# SipPuffDuoOutputsATtiny84MOSFET.net
KiCad netlist of a schematic drawn in EAGLE
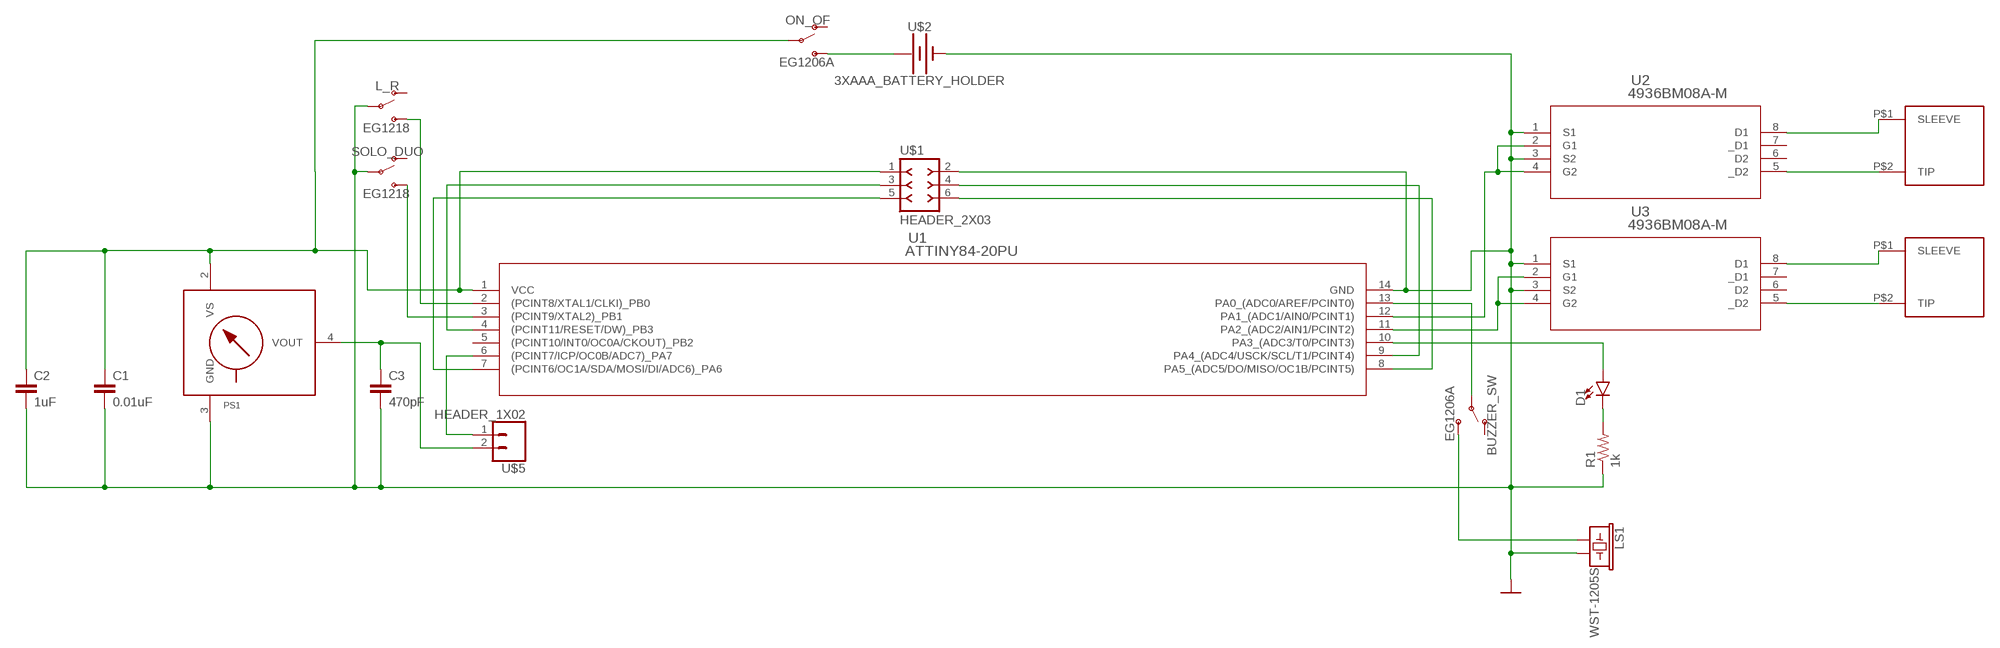
[diagram p0: schematic, sheet 1]

(export (version "E")
  (design (tool "Eeschema 10.0.6"))
  (components
    (comp (ref "BUZZER_SW")
      (value "EG1206A")
      (footprint "eagle-import:EG1206A")
      (libsource (lib "eagle-import") (part "EG1206A"))
    )
    (comp (ref "C1")
      (value "0.01uF")
      (footprint "eagle-import:CAP-PTH-SMALL-KIT")
      (libsource (lib "eagle-import") (part "0.1UF-KIT-EZ-50V-20%"))
    )
    (comp (ref "C2")
      (value "1uF")
      (footprint "eagle-import:CAP-PTH-SMALL-KIT")
      (libsource (lib "eagle-import") (part "0.1UF-KIT-EZ-50V-20%"))
    )
    (comp (ref "C3")
      (value "470pF")
      (footprint "eagle-import:CAP-PTH-SMALL-KIT")
      (libsource (lib "eagle-import") (part "0.1UF-KIT-EZ-50V-20%"))
    )
    (comp (ref "D1")
      (value "LED5MM")
      (footprint "eagle-import:LED_5MM")
      (libsource (lib "eagle-import") (part "LED5MM"))
    )
    (comp (ref "LS1")
      (value "WST-1205S")
      (footprint "eagle-import:BUZZER-12MM")
      (libsource (lib "eagle-import") (part "BUZZER-PTH"))
    )
    (comp (ref "L_R")
      (value "EG1218")
      (footprint "eagle-import:EG1218")
      (libsource (lib "eagle-import") (part "EG1218"))
    )
    (comp (ref "ON_OF")
      (value "EG1206A")
      (footprint "eagle-import:EG1206A")
      (libsource (lib "eagle-import") (part "EG1206A"))
    )
    (comp (ref "PS1")
      (value "MPX-1351")
      (footprint "eagle-import:1351")
      (libsource (lib "eagle-import") (part "MPX-1351"))
    )
    (comp (ref "R1")
      (value "1k")
      (footprint "eagle-import:RESISTOR_0207_10")
      (libsource (lib "eagle-import") (part "RESISTOR_R-US_"))
    )
    (comp (ref "SOLO_DUO")
      (value "EG1218")
      (footprint "eagle-import:EG1218")
      (libsource (lib "eagle-import") (part "EG1218"))
    )
    (comp (ref "U$1")
      (value "HEADER_2X03")
      (footprint "eagle-import:2X3")
      (libsource (lib "eagle-import") (part "HEADER_2X03"))
    )
    (comp (ref "U$2")
      (value "3XAAA_BATTERY_HOLDER")
      (footprint "eagle-import:3XAAA_BATTERY_HOLDER")
      (libsource (lib "eagle-import") (part "3XAAA_BATTERY_HOLDER"))
    )
    (comp (ref "U$3")
      (value "MONO_WIRE")
      (footprint "eagle-import:MONO_WIRE")
      (libsource (lib "eagle-import") (part "MONO_WIRE"))
    )
    (comp (ref "U$4")
      (value "MONO_WIRE")
      (footprint "eagle-import:MONO_WIRE")
      (libsource (lib "eagle-import") (part "MONO_WIRE"))
    )
    (comp (ref "U$5")
      (value "HEADER_1X02")
      (footprint "eagle-import:1X02")
      (libsource (lib "eagle-import") (part "HEADER_1X02"))
    )
    (comp (ref "U1")
      (value "ATTINY84-20PU")
      (footprint "eagle-import:14P3")
      (fields (field (name "MANUFACTURER_PART_NUMBER") "ATTINY8420PU"))
      (libsource (lib "eagle-import") (part "ATTINY84-20PU"))
    )
    (comp (ref "U2")
      (value "4936BM08A-M")
      (footprint "eagle-import:M08A-M")
      (fields (field (name "MANUFACTURER_PART_NUMBER") "LM34DM"))
      (libsource (lib "eagle-import") (part "4936BM08A-M"))
    )
    (comp (ref "U3")
      (value "4936BM08A-M")
      (footprint "eagle-import:M08A-M")
      (fields (field (name "MANUFACTURER_PART_NUMBER") "LM34DM"))
      (libsource (lib "eagle-import") (part "4936BM08A-M"))
    )
  )
  (nets
    (net (code "1") (name "GND") (class "Default")
      (node (ref "C1") (pin "2") (pinfunction "2_2") (pintype "passive"))
      (node (ref "C2") (pin "2") (pinfunction "2_2") (pintype "passive"))
      (node (ref "C3") (pin "2") (pinfunction "2_2") (pintype "passive"))
      (node (ref "LS1") (pin "-") (pinfunction "2_-") (pintype "passive"))
      (node (ref "L_R") (pin "2") (pinfunction "P_2") (pintype "passive"))
      (node (ref "PS1") (pin "3") (pinfunction "GND_3") (pintype "power_in"))
      (node (ref "R1") (pin "1") (pinfunction "1_1") (pintype "passive"))
      (node (ref "SOLO_DUO") (pin "2") (pinfunction "P_2") (pintype "passive"))
      (node (ref "U$1") (pin "2") (pinfunction "2_2") (pintype "passive"))
      (node (ref "U$2") (pin "P$2") (pinfunction "-_P$2") (pintype "power_in"))
      (node (ref "U1") (pin "14") (pinfunction "GND_14") (pintype "power_in"))
      (node (ref "U2") (pin "1") (pinfunction "S1_1") (pintype "output"))
      (node (ref "U2") (pin "3") (pinfunction "S2_3") (pintype "passive"))
      (node (ref "U3") (pin "1") (pinfunction "S1_1") (pintype "output"))
      (node (ref "U3") (pin "3") (pinfunction "S2_3") (pintype "passive"))
    )
    (net (code "2") (name "Net-(BUZZER_SW-P)") (class "Default")
      (node (ref "BUZZER_SW") (pin "2") (pinfunction "P_2") (pintype "passive"))
      (node (ref "U1") (pin "13") (pinfunction "PA0_(ADC0/AREF/PCINT0)_13") (pintype "bidirectional"))
    )
    (net (code "3") (name "Net-(BUZZER_SW-S)") (class "Default")
      (node (ref "BUZZER_SW") (pin "3") (pinfunction "S_3") (pintype "passive"))
      (node (ref "LS1") (pin "+") (pinfunction "1_+") (pintype "passive"))
    )
    (net (code "4") (name "Net-(D1-C)") (class "Default")
      (node (ref "D1") (pin "K") (pinfunction "C_K") (pintype "passive"))
      (node (ref "R1") (pin "2") (pinfunction "2_2") (pintype "passive"))
    )
    (net (code "5") (name "Net-(L_R-S)") (class "Default")
      (node (ref "L_R") (pin "3") (pinfunction "S_3") (pintype "passive"))
      (node (ref "U1") (pin "2") (pinfunction "(PCINT8/XTAL1/CLKI)_PB0_2") (pintype "bidirectional"))
    )
    (net (code "6") (name "Net-(ON_OF-P)") (class "Default")
      (node (ref "C1") (pin "1") (pinfunction "1_1") (pintype "passive"))
      (node (ref "C2") (pin "1") (pinfunction "1_1") (pintype "passive"))
      (node (ref "ON_OF") (pin "2") (pinfunction "P_2") (pintype "passive"))
      (node (ref "PS1") (pin "2") (pinfunction "VS_2") (pintype "power_in"))
      (node (ref "U$1") (pin "1") (pinfunction "1_1") (pintype "passive"))
      (node (ref "U1") (pin "1") (pinfunction "VCC_1") (pintype "power_in"))
    )
    (net (code "7") (name "Net-(ON_OF-S)") (class "Default")
      (node (ref "ON_OF") (pin "3") (pinfunction "S_3") (pintype "passive"))
      (node (ref "U$2") (pin "P$1") (pinfunction "+_P$1") (pintype "power_in"))
    )
    (net (code "8") (name "Net-(PS1-VOUT)") (class "Default")
      (node (ref "C3") (pin "1") (pinfunction "1_1") (pintype "passive"))
      (node (ref "PS1") (pin "4") (pinfunction "VOUT_4") (pintype "output"))
      (node (ref "U$5") (pin "2") (pinfunction "2_2") (pintype "passive"))
    )
    (net (code "9") (name "Net-(SOLO_DUO-S)") (class "Default")
      (node (ref "SOLO_DUO") (pin "3") (pinfunction "S_3") (pintype "passive"))
      (node (ref "U1") (pin "3") (pinfunction "(PCINT9/XTAL2)_PB1_3") (pintype "bidirectional"))
    )
    (net (code "10") (name "Net-(U$3-SLEEVE)") (class "Default")
      (node (ref "U$3") (pin "P$1") (pinfunction "SLEEVE_P$1") (pintype "bidirectional"))
      (node (ref "U2") (pin "8") (pinfunction "D1_8") (pintype "input"))
    )
    (net (code "11") (name "Net-(U$3-TIP)") (class "Default")
      (node (ref "U$3") (pin "P$2") (pinfunction "TIP_P$2") (pintype "bidirectional"))
      (node (ref "U2") (pin "5") (pinfunction "_D2_5") (pintype "passive"))
    )
    (net (code "12") (name "Net-(U$4-SLEEVE)") (class "Default")
      (node (ref "U$4") (pin "P$1") (pinfunction "SLEEVE_P$1") (pintype "bidirectional"))
      (node (ref "U3") (pin "8") (pinfunction "D1_8") (pintype "input"))
    )
    (net (code "13") (name "Net-(U$4-TIP)") (class "Default")
      (node (ref "U$4") (pin "P$2") (pinfunction "TIP_P$2") (pintype "bidirectional"))
      (node (ref "U3") (pin "5") (pinfunction "_D2_5") (pintype "passive"))
    )
    (net (code "14") (name "Net-(U1-(PCINT6{slash}OC1A{slash}SDA{slash}MOSI{slash}DI{slash}ADC6)_PA6)") (class "Default")
      (node (ref "U$1") (pin "5") (pinfunction "5_5") (pintype "passive"))
      (node (ref "U1") (pin "7") (pinfunction "(PCINT6/OC1A/SDA/MOSI/DI/ADC6)_PA6_7") (pintype "bidirectional"))
    )
    (net (code "15") (name "Net-(U1-(PCINT7{slash}ICP{slash}OC0B{slash}ADC7)_PA7)") (class "Default")
      (node (ref "U$5") (pin "1") (pinfunction "1_1") (pintype "passive"))
      (node (ref "U1") (pin "6") (pinfunction "(PCINT7/ICP/OC0B/ADC7)_PA7_6") (pintype "bidirectional"))
    )
    (net (code "16") (name "Net-(U1-(PCINT11{slash}RESET{slash}DW)_PB3)") (class "Default")
      (node (ref "U$1") (pin "3") (pinfunction "3_3") (pintype "passive"))
      (node (ref "U1") (pin "4") (pinfunction "(PCINT11/RESET/DW)_PB3_4") (pintype "bidirectional"))
    )
    (net (code "17") (name "Net-(U1-PA1_(ADC1{slash}AIN0{slash}PCINT1))") (class "Default")
      (node (ref "U1") (pin "12") (pinfunction "PA1_(ADC1/AIN0/PCINT1)_12") (pintype "bidirectional"))
      (node (ref "U2") (pin "2") (pinfunction "G1_2") (pintype "passive"))
      (node (ref "U2") (pin "4") (pinfunction "G2_4") (pintype "power_in"))
    )
    (net (code "18") (name "Net-(U1-PA2_(ADC2{slash}AIN1{slash}PCINT2))") (class "Default")
      (node (ref "U1") (pin "11") (pinfunction "PA2_(ADC2/AIN1/PCINT2)_11") (pintype "bidirectional"))
      (node (ref "U3") (pin "2") (pinfunction "G1_2") (pintype "passive"))
      (node (ref "U3") (pin "4") (pinfunction "G2_4") (pintype "power_in"))
    )
    (net (code "19") (name "Net-(U1-PA3_(ADC3{slash}T0{slash}PCINT3))") (class "Default")
      (node (ref "D1") (pin "A") (pinfunction "A_A") (pintype "passive"))
      (node (ref "U1") (pin "10") (pinfunction "PA3_(ADC3/T0/PCINT3)_10") (pintype "bidirectional"))
    )
    (net (code "20") (name "Net-(U1-PA4_(ADC4{slash}USCK{slash}SCL{slash}T1{slash}PCINT4))") (class "Default")
      (node (ref "U$1") (pin "4") (pinfunction "4_4") (pintype "passive"))
      (node (ref "U1") (pin "9") (pinfunction "PA4_(ADC4/USCK/SCL/T1/PCINT4)_9") (pintype "bidirectional"))
    )
    (net (code "21") (name "Net-(U1-PA5_(ADC5{slash}DO{slash}MISO{slash}OC1B{slash}PCINT5))") (class "Default")
      (node (ref "U$1") (pin "6") (pinfunction "6_6") (pintype "passive"))
      (node (ref "U1") (pin "8") (pinfunction "PA5_(ADC5/DO/MISO/OC1B/PCINT5)_8") (pintype "bidirectional"))
    )
    (net (code "22") (name "unconnected-(BUZZER_SW-O-Pad1)") (class "Default")
      (node (ref "BUZZER_SW") (pin "1") (pinfunction "O_1") (pintype "passive"))
    )
    (net (code "23") (name "unconnected-(L_R-O-Pad1)") (class "Default")
      (node (ref "L_R") (pin "1") (pinfunction "O_1") (pintype "passive"))
    )
    (net (code "24") (name "unconnected-(ON_OF-O-Pad1)") (class "Default")
      (node (ref "ON_OF") (pin "1") (pinfunction "O_1") (pintype "passive"))
    )
    (net (code "25") (name "unconnected-(PS1-NC-Pad1)") (class "Default")
      (node (ref "PS1") (pin "1") (pinfunction "NC_1") (pintype "no_connect"))
    )
    (net (code "26") (name "unconnected-(PS1-NC-Pad5)") (class "Default")
      (node (ref "PS1") (pin "5") (pinfunction "NC_5") (pintype "no_connect"))
    )
    (net (code "27") (name "unconnected-(PS1-NC-Pad6)") (class "Default")
      (node (ref "PS1") (pin "6") (pinfunction "NC_6") (pintype "no_connect"))
    )
    (net (code "28") (name "unconnected-(SOLO_DUO-O-Pad1)") (class "Default")
      (node (ref "SOLO_DUO") (pin "1") (pinfunction "O_1") (pintype "passive"))
    )
    (net (code "29") (name "unconnected-(U1-(PCINT10{slash}INT0{slash}OC0A{slash}CKOUT)_PB2-Pad5)") (class "Default")
      (node (ref "U1") (pin "5") (pinfunction "(PCINT10/INT0/OC0A/CKOUT)_PB2_5") (pintype "bidirectional"))
    )
    (net (code "30") (name "unconnected-(U2-D2-Pad6)") (class "Default")
      (node (ref "U2") (pin "6") (pinfunction "D2_6") (pintype "passive"))
    )
    (net (code "31") (name "unconnected-(U2-_D1-Pad7)") (class "Default")
      (node (ref "U2") (pin "7") (pinfunction "_D1_7") (pintype "passive"))
    )
    (net (code "32") (name "unconnected-(U3-D2-Pad6)") (class "Default")
      (node (ref "U3") (pin "6") (pinfunction "D2_6") (pintype "passive"))
    )
    (net (code "33") (name "unconnected-(U3-_D1-Pad7)") (class "Default")
      (node (ref "U3") (pin "7") (pinfunction "_D1_7") (pintype "passive"))
    )
  )
)
